# Transistor_as_Switch.net
KiCad netlist of a schematic drawn in EAGLE
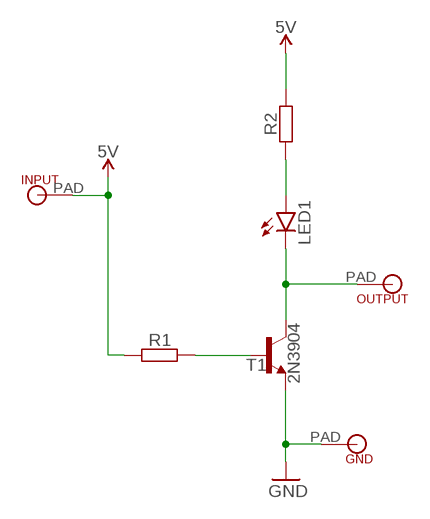
[diagram p0: schematic, sheet 1]

(export (version "E")
  (design (tool "Eeschema 10.0.6"))
  (components
    (comp (ref "GND")
      (value "MICROBIT_PAD")
      (footprint "eagle-import:MICROBIT_PAD")
      (libsource (lib "eagle-import") (part "MICROBIT_PAD"))
    )
    (comp (ref "INPUT")
      (value "MICROBIT_PAD")
      (footprint "eagle-import:MICROBIT_PAD")
      (libsource (lib "eagle-import") (part "MICROBIT_PAD"))
    )
    (comp (ref "LED1")
      (value "LEDCHIP-LED0805")
      (footprint "eagle-import:CHIP-LED0805")
      (libsource (lib "eagle-import") (part "LEDCHIP-LED0805"))
    )
    (comp (ref "OUTPUT")
      (value "MICROBIT_PAD")
      (footprint "eagle-import:MICROBIT_PAD")
      (libsource (lib "eagle-import") (part "MICROBIT_PAD"))
    )
    (comp (ref "R1")
      (value "RESISTOR-10")
      (footprint "eagle-import:R0207_10")
      (libsource (lib "eagle-import") (part "RESISTOR-10"))
    )
    (comp (ref "R2")
      (value "RESISTOR-10")
      (footprint "eagle-import:R0207_10")
      (libsource (lib "eagle-import") (part "RESISTOR-10"))
    )
    (comp (ref "T1")
      (value "2N3904")
      (footprint "eagle-import:TO92")
      (libsource (lib "eagle-import") (part "2N3904"))
    )
  )
  (nets
    (net (code "1") (name "5V") (class "Default")
      (node (ref "INPUT") (pin "PAD") (pinfunction "P$1_PAD") (pintype "bidirectional"))
      (node (ref "R1") (pin "1") (pinfunction "1_1") (pintype "passive"))
      (node (ref "R2") (pin "2") (pinfunction "2_2") (pintype "passive"))
    )
    (net (code "2") (name "GND") (class "Default")
      (node (ref "GND") (pin "PAD") (pinfunction "P$1_PAD") (pintype "bidirectional"))
      (node (ref "T1") (pin "3") (pinfunction "E_3") (pintype "passive"))
    )
    (net (code "3") (name "Net-(LED1-PadA)") (class "Default")
      (node (ref "LED1") (pin "A") (pinfunction "A_A") (pintype "passive"))
      (node (ref "R2") (pin "1") (pinfunction "1_1") (pintype "passive"))
    )
    (net (code "4") (name "Net-(OUTPUT-P$1)") (class "Default")
      (node (ref "LED1") (pin "C") (pinfunction "C_C") (pintype "passive"))
      (node (ref "OUTPUT") (pin "PAD") (pinfunction "P$1_PAD") (pintype "bidirectional"))
      (node (ref "T1") (pin "1") (pinfunction "C_1") (pintype "passive"))
    )
    (net (code "5") (name "Net-(T1-B)") (class "Default")
      (node (ref "R1") (pin "2") (pinfunction "2_2") (pintype "passive"))
      (node (ref "T1") (pin "2") (pinfunction "B_2") (pintype "passive"))
    )
  )
)
